# LEDThermometer.net
KiCad netlist of a schematic drawn in Altium Designer
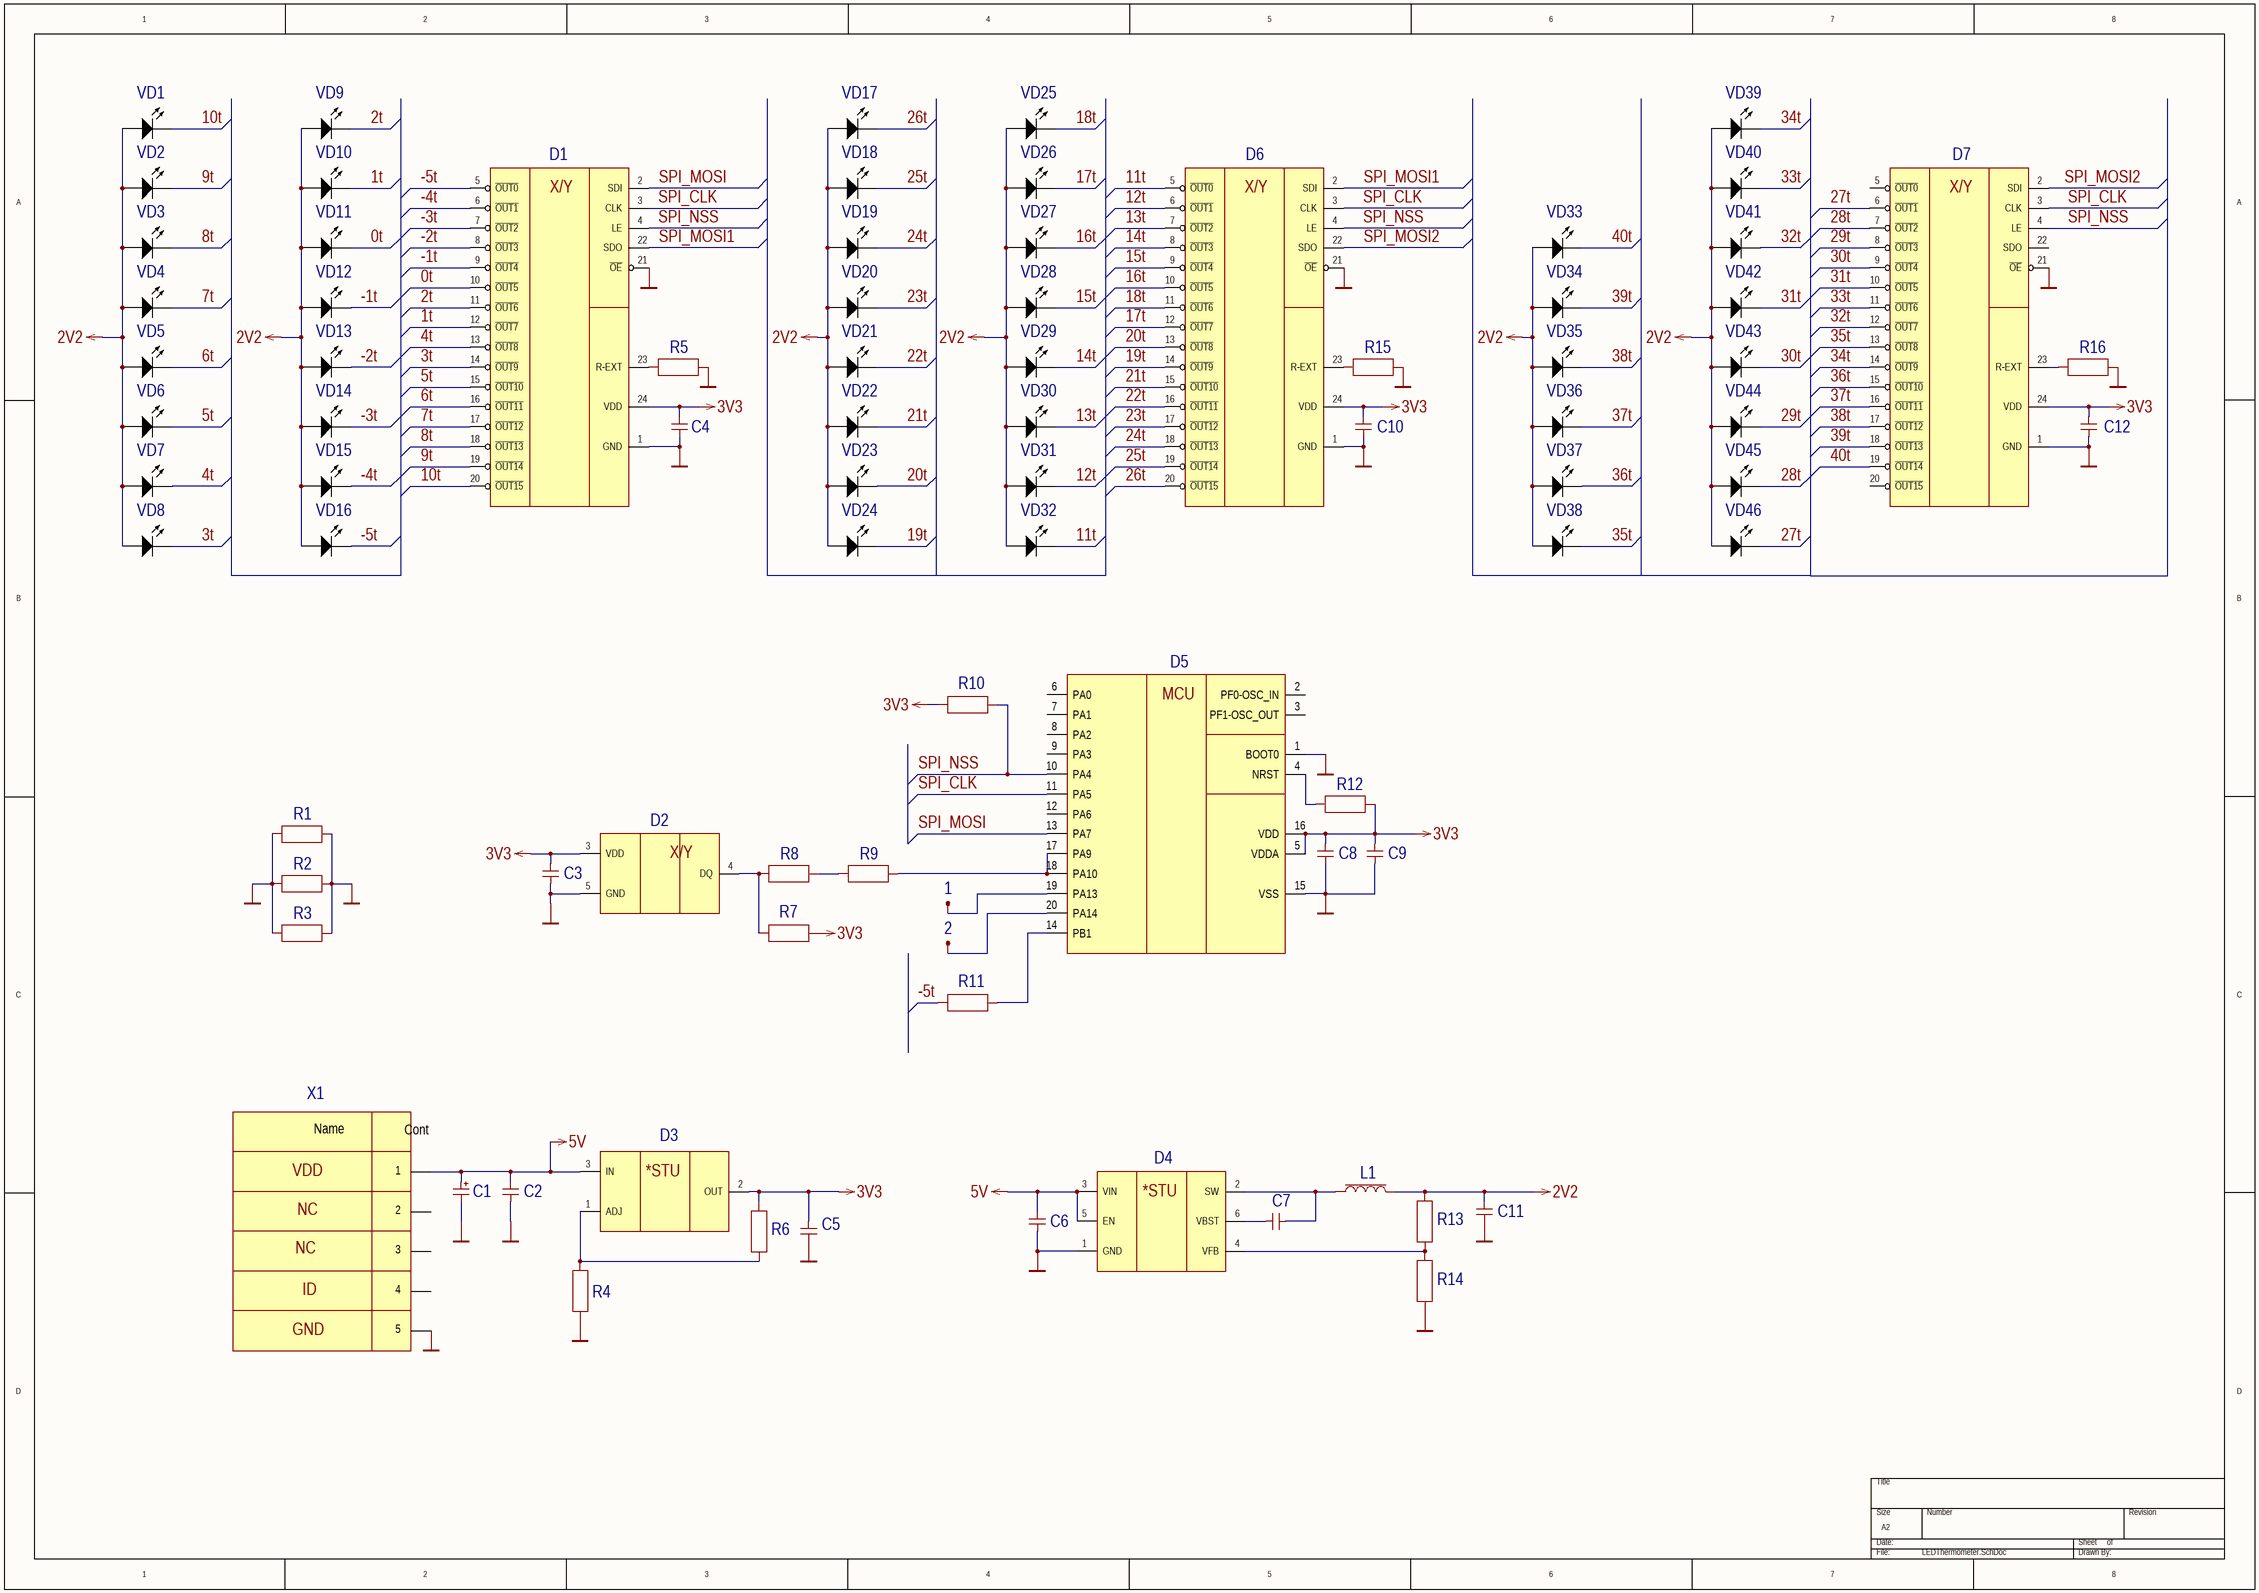
[diagram p0: LEDThermometer.SchDoc]

(export (version "E")
  (design (tool "Eeschema 10.0.6"))
  (components
    (comp (ref "1") (value "*") (footprint "point") (libsource (lib "Passive,Diodes") (part "Point")))
    (comp (ref "2") (value "*") (footprint "point") (libsource (lib "Passive,Diodes") (part "Point")))
    (comp (ref "C1")
      (value "D-20 V-47uF±10 %")
      (footprint "CAP POL 2917/7343")
      (description "Electrolytic capacitor")
      (libsource (lib "Passive,Diodes") (part "Cap_el"))
    )
    (comp (ref "C2")
      (value "0805-16 V-X7R-1uF±10 %")
      (footprint "SMD-0805C")
      (description "Capacitor")
      (libsource (lib "Passive,Diodes") (part "Cap"))
    )
    (comp (ref "C3")
      (value "0805-16 V-X7R-0.1uF±10 %")
      (footprint "SMD-0805C")
      (description "Capacitor")
      (libsource (lib "Passive,Diodes") (part "Cap"))
    )
    (comp (ref "C4")
      (value "0805-16 V-X7R-0.1uF±10 %")
      (footprint "SMD-0805C")
      (description "Capacitor")
      (libsource (lib "Passive,Diodes") (part "Cap"))
    )
    (comp (ref "C5")
      (value "0805-16 V-X7R-1uF±10 %")
      (footprint "SMD-0805C")
      (description "Capacitor")
      (libsource (lib "Passive,Diodes") (part "Cap"))
    )
    (comp (ref "C6")
      (value "0805-16 V-X7R-0.1uF±10 %")
      (footprint "SMD-0805C")
      (description "Capacitor")
      (libsource (lib "Passive,Diodes") (part "Cap"))
    )
    (comp (ref "C7")
      (value "0805-16 V-X7R-0.1uF±10 %")
      (footprint "SMD-0805C")
      (description "Capacitor")
      (libsource (lib "Passive,Diodes") (part "Cap"))
    )
    (comp (ref "C8")
      (value "0805-16 V-X7R-0.1uF±10 %")
      (footprint "SMD-0805C")
      (description "Capacitor")
      (libsource (lib "Passive,Diodes") (part "Cap"))
    )
    (comp (ref "C9")
      (value "0805-16 V-X7R-0.1uF±10 %")
      (footprint "SMD-0805C")
      (description "Capacitor")
      (libsource (lib "Passive,Diodes") (part "Cap"))
    )
    (comp (ref "C10")
      (value "0805-16 V-X7R-0.1uF±10 %")
      (footprint "SMD-0805C")
      (description "Capacitor")
      (libsource (lib "Passive,Diodes") (part "Cap"))
    )
    (comp (ref "C11")
      (value "1206-16 V-X7R-22uF±10 %")
      (footprint "SMD-1206C")
      (description "Capacitor")
      (libsource (lib "Passive,Diodes") (part "Cap"))
    )
    (comp (ref "C12")
      (value "0805-16 V-X7R-0.1uF±10 %")
      (footprint "SMD-0805C")
      (description "Capacitor")
      (libsource (lib "Passive,Diodes") (part "Cap"))
    )
    (comp (ref "D1")
      (value "MBI5039GF-B")
      (footprint "SOP24L")
      (description "16-Channel Constant Current LED Sink Driver with Silent Error Detection and Current Gain")
      (fields (field (name "MANUFACTURER") "Macroblock"))
      (libsource (lib "Devices") (part "MBI5039"))
    )
    (comp (ref "D2")
      (value "DS18B20Z+")
      (footprint "SO8_M")
      (description "Programmable Resolution 1-Wire Digital Thermometer")
      (fields (field (name "MANUFACTURER") "Maxim Integrated"))
      (libsource (lib "Devices") (part "DS18B20"))
    )
    (comp (ref "D3")
      (value "LM317DCYR")
      (footprint "SOT223_M")
      (description "3-Terminal Adjustable Regulator")
      (fields (field (name "MANUFACTURER") "Texas Instruments"))
      (libsource (lib "Devices") (part "LM317"))
    )
    (comp (ref "D4")
      (value "TPS562200DDCT")
      (footprint "SOT23-6_M")
      (description "4.5-V To 17-V Input, 2-A, 3-A Synchronous Step-Down Voltage Regulator")
      (fields (field (name "MANUFACTURER") "Texas Instruments"))
      (libsource (lib "Devices") (part "TPS562200"))
    )
    (comp (ref "D5")
      (value "STM32F030F4P6")
      (footprint "TSSOP-20")
      (fields (field (name "MANUFACTURER") "STMicroelectronics"))
      (libsource (lib "Devices") (part "STM32F030FxP"))
    )
    (comp (ref "D6")
      (value "MBI5039GF-B")
      (footprint "SOP24L")
      (description "16-Channel Constant Current LED Sink Driver with Silent Error Detection and Current Gain")
      (fields (field (name "MANUFACTURER") "Macroblock"))
      (libsource (lib "Devices") (part "MBI5039"))
    )
    (comp (ref "D7")
      (value "MBI5039GF-B")
      (footprint "SOP24L")
      (description "16-Channel Constant Current LED Sink Driver with Silent Error Detection and Current Gain")
      (fields (field (name "MANUFACTURER") "Macroblock"))
      (libsource (lib "Devices") (part "MBI5039"))
    )
    (comp (ref "L1")
      (value "NLCV32T-2R2M-EF")
      (footprint "1210_M")
      (description "Inductor")
      (fields (field (name "MANUFACTURER") "TDK"))
      (libsource (lib "Passive,Diodes") (part "Inductor"))
    )
    (comp (ref "R1")
      (value "0805±5 %-0 Ohm")
      (footprint "SMD-0805-RES")
      (description "Resistor")
      (libsource (lib "") (part "Res_2"))
    )
    (comp (ref "R2")
      (value "0805±5 %-0 Ohm")
      (footprint "SMD-0805-RES")
      (description "Resistor")
      (libsource (lib "") (part "Res_2"))
    )
    (comp (ref "R3")
      (value "0805±5 %-0 Ohm")
      (footprint "SMD-0805-RES")
      (description "Resistor")
      (libsource (lib "") (part "Res_2"))
    )
    (comp (ref "R4")
      (value "0805±1 %-2 kOhm")
      (footprint "SMD-0805-RES")
      (description "Resistor")
      (libsource (lib "") (part "Res_3"))
    )
    (comp (ref "R5")
      (value "0805±1 %-10 kOhm")
      (footprint "SMD-0805-RES")
      (description "Resistor")
      (libsource (lib "") (part "Res_2"))
    )
    (comp (ref "R6")
      (value "0805±1 %-1.3 kOhm")
      (footprint "SMD-0805-RES")
      (description "Resistor")
      (libsource (lib "") (part "Res_2"))
    )
    (comp (ref "R7")
      (value "0805±5 %-4.7 kOhm")
      (footprint "SMD-0805-RES")
      (description "Resistor")
      (libsource (lib "") (part "Res_1"))
    )
    (comp (ref "R8")
      (value "0805±5 %-0 Ohm")
      (footprint "SMD-0805-RES")
      (description "Resistor")
      (libsource (lib "") (part "Res_2"))
    )
    (comp (ref "R9")
      (value "0805±5 %-0 Ohm")
      (footprint "SMD-0805-RES")
      (description "Resistor")
      (libsource (lib "") (part "Res_2"))
    )
    (comp (ref "R10")
      (value "0805±5 %-10 kOhm")
      (footprint "SMD-0805-RES")
      (description "Resistor")
      (libsource (lib "Passive,Diodes") (part "Res"))
    )
    (comp (ref "R11")
      (value "DNP")
      (footprint "SMD-0805-RES")
      (description "Resistor")
      (libsource (lib "Passive,Diodes") (part "Res"))
    )
    (comp (ref "R12")
      (value "0805±5 %-10 kOhm")
      (footprint "SMD-0805-RES")
      (description "Resistor")
      (libsource (lib "") (part "Res_2"))
    )
    (comp (ref "R13")
      (value "0805±1 %-19.6 kOhm")
      (footprint "SMD-0805-RES")
      (description "Resistor")
      (libsource (lib "") (part "Res_2"))
    )
    (comp (ref "R14")
      (value "0805±1 %-10.2 kOhm")
      (footprint "SMD-0805-RES")
      (description "Resistor")
      (libsource (lib "") (part "Res_2"))
    )
    (comp (ref "R15")
      (value "0805±1 %-10 kOhm")
      (footprint "SMD-0805-RES")
      (description "Resistor")
      (libsource (lib "") (part "Res_2"))
    )
    (comp (ref "R16")
      (value "0805±1 %-10 kOhm")
      (footprint "SMD-0805-RES")
      (description "Resistor")
      (libsource (lib "") (part "Res_2"))
    )
    (comp (ref "VD1")
      (value "L-144IDT")
      (footprint "LED_1.9x3.9mm")
      (description "Typical INFRARED GaAs LED")
      (fields (field (name "MANUFACTURER") "Kingbright"))
      (libsource (lib "Passive,Diodes") (part "LED"))
    )
    (comp (ref "VD2")
      (value "L-144IDT")
      (footprint "LED_1.9x3.9mm")
      (description "Typical INFRARED GaAs LED")
      (fields (field (name "MANUFACTURER") "Kingbright"))
      (libsource (lib "Passive,Diodes") (part "LED"))
    )
    (comp (ref "VD3")
      (value "L-144IDT")
      (footprint "LED_1.9x3.9mm")
      (description "Typical INFRARED GaAs LED")
      (fields (field (name "MANUFACTURER") "Kingbright"))
      (libsource (lib "Passive,Diodes") (part "LED"))
    )
    (comp (ref "VD4")
      (value "L-144IDT")
      (footprint "LED_1.9x3.9mm")
      (description "Typical INFRARED GaAs LED")
      (fields (field (name "MANUFACTURER") "Kingbright"))
      (libsource (lib "Passive,Diodes") (part "LED"))
    )
    (comp (ref "VD5")
      (value "L-144IDT")
      (footprint "LED_1.9x3.9mm")
      (description "Typical INFRARED GaAs LED")
      (fields (field (name "MANUFACTURER") "Kingbright"))
      (libsource (lib "Passive,Diodes") (part "LED"))
    )
    (comp (ref "VD6")
      (value "L-144IDT")
      (footprint "LED_1.9x3.9mm")
      (description "Typical INFRARED GaAs LED")
      (fields (field (name "MANUFACTURER") "Kingbright"))
      (libsource (lib "Passive,Diodes") (part "LED"))
    )
    (comp (ref "VD7")
      (value "L-144IDT")
      (footprint "LED_1.9x3.9mm")
      (description "Typical INFRARED GaAs LED")
      (fields (field (name "MANUFACTURER") "Kingbright"))
      (libsource (lib "Passive,Diodes") (part "LED"))
    )
    (comp (ref "VD8")
      (value "L-144IDT")
      (footprint "LED_1.9x3.9mm")
      (description "Typical INFRARED GaAs LED")
      (fields (field (name "MANUFACTURER") "Kingbright"))
      (libsource (lib "Passive,Diodes") (part "LED"))
    )
    (comp (ref "VD9")
      (value "L-144IDT")
      (footprint "LED_1.9x3.9mm")
      (description "Typical INFRARED GaAs LED")
      (fields (field (name "MANUFACTURER") "Kingbright"))
      (libsource (lib "Passive,Diodes") (part "LED"))
    )
    (comp (ref "VD10")
      (value "L-144IDT")
      (footprint "LED_1.9x3.9mm")
      (description "Typical INFRARED GaAs LED")
      (fields (field (name "MANUFACTURER") "Kingbright"))
      (libsource (lib "Passive,Diodes") (part "LED"))
    )
    (comp (ref "VD11")
      (value "L-144IDT")
      (footprint "LED_1.9x3.9mm")
      (description "Typical INFRARED GaAs LED")
      (fields (field (name "MANUFACTURER") "Kingbright"))
      (libsource (lib "Passive,Diodes") (part "LED"))
    )
    (comp (ref "VD12")
      (value "L-144IDT")
      (footprint "LED_1.9x3.9mm")
      (description "Typical INFRARED GaAs LED")
      (fields (field (name "MANUFACTURER") "Kingbright"))
      (libsource (lib "Passive,Diodes") (part "LED"))
    )
    (comp (ref "VD13")
      (value "L-144IDT")
      (footprint "LED_1.9x3.9mm")
      (description "Typical INFRARED GaAs LED")
      (fields (field (name "MANUFACTURER") "Kingbright"))
      (libsource (lib "Passive,Diodes") (part "LED"))
    )
    (comp (ref "VD14")
      (value "L-144IDT")
      (footprint "LED_1.9x3.9mm")
      (description "Typical INFRARED GaAs LED")
      (fields (field (name "MANUFACTURER") "Kingbright"))
      (libsource (lib "Passive,Diodes") (part "LED"))
    )
    (comp (ref "VD15")
      (value "L-144IDT")
      (footprint "LED_1.9x3.9mm")
      (description "Typical INFRARED GaAs LED")
      (fields (field (name "MANUFACTURER") "Kingbright"))
      (libsource (lib "Passive,Diodes") (part "LED"))
    )
    (comp (ref "VD16")
      (value "L-793ID")
      (footprint "LED_8mm")
      (description "Typical INFRARED GaAs LED")
      (fields (field (name "MANUFACTURER") "Kingbright"))
      (libsource (lib "Passive,Diodes") (part "LED"))
    )
    (comp (ref "VD17")
      (value "L-144IDT")
      (footprint "LED_1.9x3.9mm")
      (description "Typical INFRARED GaAs LED")
      (fields (field (name "MANUFACTURER") "Kingbright"))
      (libsource (lib "Passive,Diodes") (part "LED"))
    )
    (comp (ref "VD18")
      (value "L-144IDT")
      (footprint "LED_1.9x3.9mm")
      (description "Typical INFRARED GaAs LED")
      (fields (field (name "MANUFACTURER") "Kingbright"))
      (libsource (lib "Passive,Diodes") (part "LED"))
    )
    (comp (ref "VD19")
      (value "L-144IDT")
      (footprint "LED_1.9x3.9mm")
      (description "Typical INFRARED GaAs LED")
      (fields (field (name "MANUFACTURER") "Kingbright"))
      (libsource (lib "Passive,Diodes") (part "LED"))
    )
    (comp (ref "VD20")
      (value "L-144IDT")
      (footprint "LED_1.9x3.9mm")
      (description "Typical INFRARED GaAs LED")
      (fields (field (name "MANUFACTURER") "Kingbright"))
      (libsource (lib "Passive,Diodes") (part "LED"))
    )
    (comp (ref "VD21")
      (value "L-144IDT")
      (footprint "LED_1.9x3.9mm")
      (description "Typical INFRARED GaAs LED")
      (fields (field (name "MANUFACTURER") "Kingbright"))
      (libsource (lib "Passive,Diodes") (part "LED"))
    )
    (comp (ref "VD22")
      (value "L-144IDT")
      (footprint "LED_1.9x3.9mm")
      (description "Typical INFRARED GaAs LED")
      (fields (field (name "MANUFACTURER") "Kingbright"))
      (libsource (lib "Passive,Diodes") (part "LED"))
    )
    (comp (ref "VD23")
      (value "L-144IDT")
      (footprint "LED_1.9x3.9mm")
      (description "Typical INFRARED GaAs LED")
      (fields (field (name "MANUFACTURER") "Kingbright"))
      (libsource (lib "Passive,Diodes") (part "LED"))
    )
    (comp (ref "VD24")
      (value "L-144IDT")
      (footprint "LED_1.9x3.9mm")
      (description "Typical INFRARED GaAs LED")
      (fields (field (name "MANUFACTURER") "Kingbright"))
      (libsource (lib "Passive,Diodes") (part "LED"))
    )
    (comp (ref "VD25")
      (value "L-144IDT")
      (footprint "LED_1.9x3.9mm")
      (description "Typical INFRARED GaAs LED")
      (fields (field (name "MANUFACTURER") "Kingbright"))
      (libsource (lib "Passive,Diodes") (part "LED"))
    )
    (comp (ref "VD26")
      (value "L-144IDT")
      (footprint "LED_1.9x3.9mm")
      (description "Typical INFRARED GaAs LED")
      (fields (field (name "MANUFACTURER") "Kingbright"))
      (libsource (lib "Passive,Diodes") (part "LED"))
    )
    (comp (ref "VD27")
      (value "L-144IDT")
      (footprint "LED_1.9x3.9mm")
      (description "Typical INFRARED GaAs LED")
      (fields (field (name "MANUFACTURER") "Kingbright"))
      (libsource (lib "Passive,Diodes") (part "LED"))
    )
    (comp (ref "VD28")
      (value "L-144IDT")
      (footprint "LED_1.9x3.9mm")
      (description "Typical INFRARED GaAs LED")
      (fields (field (name "MANUFACTURER") "Kingbright"))
      (libsource (lib "Passive,Diodes") (part "LED"))
    )
    (comp (ref "VD29")
      (value "L-144IDT")
      (footprint "LED_1.9x3.9mm")
      (description "Typical INFRARED GaAs LED")
      (fields (field (name "MANUFACTURER") "Kingbright"))
      (libsource (lib "Passive,Diodes") (part "LED"))
    )
    (comp (ref "VD30")
      (value "L-144IDT")
      (footprint "LED_1.9x3.9mm")
      (description "Typical INFRARED GaAs LED")
      (fields (field (name "MANUFACTURER") "Kingbright"))
      (libsource (lib "Passive,Diodes") (part "LED"))
    )
    (comp (ref "VD31")
      (value "L-144IDT")
      (footprint "LED_1.9x3.9mm")
      (description "Typical INFRARED GaAs LED")
      (fields (field (name "MANUFACTURER") "Kingbright"))
      (libsource (lib "Passive,Diodes") (part "LED"))
    )
    (comp (ref "VD32")
      (value "L-144IDT")
      (footprint "LED_1.9x3.9mm")
      (description "Typical INFRARED GaAs LED")
      (fields (field (name "MANUFACTURER") "Kingbright"))
      (libsource (lib "Passive,Diodes") (part "LED"))
    )
    (comp (ref "VD33")
      (value "L-144IDT")
      (footprint "LED_1.9x3.9mm")
      (description "Typical INFRARED GaAs LED")
      (fields (field (name "MANUFACTURER") "Kingbright"))
      (libsource (lib "Passive,Diodes") (part "LED"))
    )
    (comp (ref "VD34")
      (value "L-144IDT")
      (footprint "LED_1.9x3.9mm")
      (description "Typical INFRARED GaAs LED")
      (fields (field (name "MANUFACTURER") "Kingbright"))
      (libsource (lib "Passive,Diodes") (part "LED"))
    )
    (comp (ref "VD35")
      (value "L-144IDT")
      (footprint "LED_1.9x3.9mm")
      (description "Typical INFRARED GaAs LED")
      (fields (field (name "MANUFACTURER") "Kingbright"))
      (libsource (lib "Passive,Diodes") (part "LED"))
    )
    (comp (ref "VD36")
      (value "L-144IDT")
      (footprint "LED_1.9x3.9mm")
      (description "Typical INFRARED GaAs LED")
      (fields (field (name "MANUFACTURER") "Kingbright"))
      (libsource (lib "Passive,Diodes") (part "LED"))
    )
    (comp (ref "VD37")
      (value "L-144IDT")
      (footprint "LED_1.9x3.9mm")
      (description "Typical INFRARED GaAs LED")
      (fields (field (name "MANUFACTURER") "Kingbright"))
      (libsource (lib "Passive,Diodes") (part "LED"))
    )
    (comp (ref "VD38")
      (value "L-144IDT")
      (footprint "LED_1.9x3.9mm")
      (description "Typical INFRARED GaAs LED")
      (fields (field (name "MANUFACTURER") "Kingbright"))
      (libsource (lib "Passive,Diodes") (part "LED"))
    )
    (comp (ref "VD39")
      (value "L-144IDT")
      (footprint "LED_1.9x3.9mm")
      (description "Typical INFRARED GaAs LED")
      (fields (field (name "MANUFACTURER") "Kingbright"))
      (libsource (lib "Passive,Diodes") (part "LED"))
    )
    (comp (ref "VD40")
      (value "L-144IDT")
      (footprint "LED_1.9x3.9mm")
      (description "Typical INFRARED GaAs LED")
      (fields (field (name "MANUFACTURER") "Kingbright"))
      (libsource (lib "Passive,Diodes") (part "LED"))
    )
    (comp (ref "VD41")
      (value "L-144IDT")
      (footprint "LED_1.9x3.9mm")
      (description "Typical INFRARED GaAs LED")
      (fields (field (name "MANUFACTURER") "Kingbright"))
      (libsource (lib "Passive,Diodes") (part "LED"))
    )
    (comp (ref "VD42")
      (value "L-144IDT")
      (footprint "LED_1.9x3.9mm")
      (description "Typical INFRARED GaAs LED")
      (fields (field (name "MANUFACTURER") "Kingbright"))
      (libsource (lib "Passive,Diodes") (part "LED"))
    )
    (comp (ref "VD43")
      (value "L-144IDT")
      (footprint "LED_1.9x3.9mm")
      (description "Typical INFRARED GaAs LED")
      (fields (field (name "MANUFACTURER") "Kingbright"))
      (libsource (lib "Passive,Diodes") (part "LED"))
    )
    (comp (ref "VD44")
      (value "L-144IDT")
      (footprint "LED_1.9x3.9mm")
      (description "Typical INFRARED GaAs LED")
      (fields (field (name "MANUFACTURER") "Kingbright"))
      (libsource (lib "Passive,Diodes") (part "LED"))
    )
    (comp (ref "VD45")
      (value "L-144IDT")
      (footprint "LED_1.9x3.9mm")
      (description "Typical INFRARED GaAs LED")
      (fields (field (name "MANUFACTURER") "Kingbright"))
      (libsource (lib "Passive,Diodes") (part "LED"))
    )
    (comp (ref "VD46")
      (value "L-144IDT")
      (footprint "LED_1.9x3.9mm")
      (description "Typical INFRARED GaAs LED")
      (fields (field (name "MANUFACTURER") "Kingbright"))
      (libsource (lib "Passive,Diodes") (part "LED"))
    )
    (comp (ref "X1")
      (value "DS1104-B60SRS")
      (footprint "Mini-USB-B")
      (description "Mini USB-B connector")
      (fields (field (name "MANUFACTURER") "Connfly Electronics"))
      (libsource (lib "Connectors") (part "MINI-USB-B"))
    )
  )
  (nets
    (net (code "1") (name "/-1t") (class "Default")
      (node (ref "D1") (pin "9") (pinfunction "~{OUT4}_9") (pintype "passive"))
      (node (ref "VD12") (pin "2") (pinfunction "K_2") (pintype "passive"))
    )
    (net (code "2") (name "/-2t") (class "Default")
      (node (ref "D1") (pin "8") (pinfunction "~{OUT3}_8") (pintype "passive"))
      (node (ref "VD13") (pin "2") (pinfunction "K_2") (pintype "passive"))
    )
    (net (code "3") (name "/-3t") (class "Default")
      (node (ref "D1") (pin "7") (pinfunction "~{OUT2}_7") (pintype "passive"))
      (node (ref "VD14") (pin "2") (pinfunction "K_2") (pintype "passive"))
    )
    (net (code "4") (name "/-4t") (class "Default")
      (node (ref "D1") (pin "6") (pinfunction "~{OUT1}_6") (pintype "passive"))
      (node (ref "VD15") (pin "2") (pinfunction "K_2") (pintype "passive"))
    )
    (net (code "5") (name "/-5t") (class "Default")
      (node (ref "D1") (pin "5") (pinfunction "~{OUT0}_5") (pintype "passive"))
      (node (ref "R11") (pin "1") (pinfunction "1_1") (pintype "passive"))
      (node (ref "VD16") (pin "2") (pinfunction "K_2") (pintype "passive"))
    )
    (net (code "6") (name "/0t") (class "Default")
      (node (ref "D1") (pin "10") (pinfunction "~{OUT5}_10") (pintype "passive"))
      (node (ref "VD11") (pin "2") (pinfunction "K_2") (pintype "passive"))
    )
    (net (code "7") (name "/1t") (class "Default")
      (node (ref "D1") (pin "12") (pinfunction "~{OUT7}_12") (pintype "passive"))
      (node (ref "VD10") (pin "2") (pinfunction "K_2") (pintype "passive"))
    )
    (net (code "8") (name "/2t") (class "Default")
      (node (ref "D1") (pin "11") (pinfunction "~{OUT6}_11") (pintype "passive"))
      (node (ref "VD9") (pin "2") (pinfunction "K_2") (pintype "passive"))
    )
    (net (code "9") (name "/3t") (class "Default")
      (node (ref "D1") (pin "14") (pinfunction "~{OUT9}_14") (pintype "passive"))
      (node (ref "VD8") (pin "2") (pinfunction "K_2") (pintype "passive"))
    )
    (net (code "10") (name "/4t") (class "Default")
      (node (ref "D1") (pin "13") (pinfunction "~{OUT8}_13") (pintype "passive"))
      (node (ref "VD7") (pin "2") (pinfunction "K_2") (pintype "passive"))
    )
    (net (code "11") (name "/5t") (class "Default")
      (node (ref "D1") (pin "15") (pinfunction "~{OUT10}_15") (pintype "passive"))
      (node (ref "VD6") (pin "2") (pinfunction "K_2") (pintype "passive"))
    )
    (net (code "12") (name "/6t") (class "Default")
      (node (ref "D1") (pin "16") (pinfunction "~{OUT11}_16") (pintype "passive"))
      (node (ref "VD5") (pin "2") (pinfunction "K_2") (pintype "passive"))
    )
    (net (code "13") (name "/7t") (class "Default")
      (node (ref "D1") (pin "17") (pinfunction "~{OUT12}_17") (pintype "passive"))
      (node (ref "VD4") (pin "2") (pinfunction "K_2") (pintype "passive"))
    )
    (net (code "14") (name "/8t") (class "Default")
      (node (ref "D1") (pin "18") (pinfunction "~{OUT13}_18") (pintype "passive"))
      (node (ref "VD3") (pin "2") (pinfunction "K_2") (pintype "passive"))
    )
    (net (code "15") (name "/9t") (class "Default")
      (node (ref "D1") (pin "19") (pinfunction "~{OUT14}_19") (pintype "passive"))
      (node (ref "VD2") (pin "2") (pinfunction "K_2") (pintype "passive"))
    )
    (net (code "16") (name "/10t") (class "Default")
      (node (ref "D1") (pin "20") (pinfunction "~{OUT15}_20") (pintype "passive"))
      (node (ref "VD1") (pin "2") (pinfunction "K_2") (pintype "passive"))
    )
    (net (code "17") (name "/11t") (class "Default")
      (node (ref "D6") (pin "5") (pinfunction "~{OUT0}_5") (pintype "passive"))
      (node (ref "VD32") (pin "2") (pinfunction "K_2") (pintype "passive"))
    )
    (net (code "18") (name "/12t") (class "Default")
      (node (ref "D6") (pin "6") (pinfunction "~{OUT1}_6") (pintype "passive"))
      (node (ref "VD31") (pin "2") (pinfunction "K_2") (pintype "passive"))
    )
    (net (code "19") (name "/13t") (class "Default")
      (node (ref "D6") (pin "7") (pinfunction "~{OUT2}_7") (pintype "passive"))
      (node (ref "VD30") (pin "2") (pinfunction "K_2") (pintype "passive"))
    )
    (net (code "20") (name "/14t") (class "Default")
      (node (ref "D6") (pin "8") (pinfunction "~{OUT3}_8") (pintype "passive"))
      (node (ref "VD29") (pin "2") (pinfunction "K_2") (pintype "passive"))
    )
    (net (code "21") (name "/15t") (class "Default")
      (node (ref "D6") (pin "9") (pinfunction "~{OUT4}_9") (pintype "passive"))
      (node (ref "VD28") (pin "2") (pinfunction "K_2") (pintype "passive"))
    )
    (net (code "22") (name "/16t") (class "Default")
      (node (ref "D6") (pin "10") (pinfunction "~{OUT5}_10") (pintype "passive"))
      (node (ref "VD27") (pin "2") (pinfunction "K_2") (pintype "passive"))
    )
    (net (code "23") (name "/17t") (class "Default")
      (node (ref "D6") (pin "12") (pinfunction "~{OUT7}_12") (pintype "passive"))
      (node (ref "VD26") (pin "2") (pinfunction "K_2") (pintype "passive"))
    )
    (net (code "24") (name "/18t") (class "Default")
      (node (ref "D6") (pin "11") (pinfunction "~{OUT6}_11") (pintype "passive"))
      (node (ref "VD25") (pin "2") (pinfunction "K_2") (pintype "passive"))
    )
    (net (code "25") (name "/19t") (class "Default")
      (node (ref "D6") (pin "14") (pinfunction "~{OUT9}_14") (pintype "passive"))
      (node (ref "VD24") (pin "2") (pinfunction "K_2") (pintype "passive"))
    )
    (net (code "26") (name "/20t") (class "Default")
      (node (ref "D6") (pin "13") (pinfunction "~{OUT8}_13") (pintype "passive"))
      (node (ref "VD23") (pin "2") (pinfunction "K_2") (pintype "passive"))
    )
    (net (code "27") (name "/21t") (class "Default")
      (node (ref "D6") (pin "15") (pinfunction "~{OUT10}_15") (pintype "passive"))
      (node (ref "VD22") (pin "2") (pinfunction "K_2") (pintype "passive"))
    )
    (net (code "28") (name "/22t") (class "Default")
      (node (ref "D6") (pin "16") (pinfunction "~{OUT11}_16") (pintype "passive"))
      (node (ref "VD21") (pin "2") (pinfunction "K_2") (pintype "passive"))
    )
    (net (code "29") (name "/23t") (class "Default")
      (node (ref "D6") (pin "17") (pinfunction "~{OUT12}_17") (pintype "passive"))
      (node (ref "VD20") (pin "2") (pinfunction "K_2") (pintype "passive"))
    )
    (net (code "30") (name "/24t") (class "Default")
      (node (ref "D6") (pin "18") (pinfunction "~{OUT13}_18") (pintype "passive"))
      (node (ref "VD19") (pin "2") (pinfunction "K_2") (pintype "passive"))
    )
    (net (code "31") (name "/25t") (class "Default")
      (node (ref "D6") (pin "19") (pinfunction "~{OUT14}_19") (pintype "passive"))
      (node (ref "VD18") (pin "2") (pinfunction "K_2") (pintype "passive"))
    )
    (net (code "32") (name "/26t") (class "Default")
      (node (ref "D6") (pin "20") (pinfunction "~{OUT15}_20") (pintype "passive"))
      (node (ref "VD17") (pin "2") (pinfunction "K_2") (pintype "passive"))
    )
    (net (code "33") (name "/27t") (class "Default")
      (node (ref "D7") (pin "6") (pinfunction "~{OUT1}_6") (pintype "passive"))
      (node (ref "VD46") (pin "2") (pinfunction "K_2") (pintype "passive"))
    )
    (net (code "34") (name "/28t") (class "Default")
      (node (ref "D7") (pin "7") (pinfunction "~{OUT2}_7") (pintype "passive"))
      (node (ref "VD45") (pin "2") (pinfunction "K_2") (pintype "passive"))
    )
    (net (code "35") (name "/29t") (class "Default")
      (node (ref "D7") (pin "8") (pinfunction "~{OUT3}_8") (pintype "passive"))
      (node (ref "VD44") (pin "2") (pinfunction "K_2") (pintype "passive"))
    )
    (net (code "36") (name "/30t") (class "Default")
      (node (ref "D7") (pin "9") (pinfunction "~{OUT4}_9") (pintype "passive"))
      (node (ref "VD43") (pin "2") (pinfunction "K_2") (pintype "passive"))
    )
    (net (code "37") (name "/31t") (class "Default")
      (node (ref "D7") (pin "10") (pinfunction "~{OUT5}_10") (pintype "passive"))
      (node (ref "VD42") (pin "2") (pinfunction "K_2") (pintype "passive"))
    )
    (net (code "38") (name "/32t") (class "Default")
      (node (ref "D7") (pin "12") (pinfunction "~{OUT7}_12") (pintype "passive"))
      (node (ref "VD41") (pin "2") (pinfunction "K_2") (pintype "passive"))
    )
    (net (code "39") (name "/33t") (class "Default")
      (node (ref "D7") (pin "11") (pinfunction "~{OUT6}_11") (pintype "passive"))
      (node (ref "VD40") (pin "2") (pinfunction "K_2") (pintype "passive"))
    )
    (net (code "40") (name "/34t") (class "Default")
      (node (ref "D7") (pin "14") (pinfunction "~{OUT9}_14") (pintype "passive"))
      (node (ref "VD39") (pin "2") (pinfunction "K_2") (pintype "passive"))
    )
    (net (code "41") (name "/35t") (class "Default")
      (node (ref "D7") (pin "13") (pinfunction "~{OUT8}_13") (pintype "passive"))
      (node (ref "VD38") (pin "2") (pinfunction "K_2") (pintype "passive"))
    )
    (net (code "42") (name "/36t") (class "Default")
      (node (ref "D7") (pin "15") (pinfunction "~{OUT10}_15") (pintype "passive"))
      (node (ref "VD37") (pin "2") (pinfunction "K_2") (pintype "passive"))
    )
    (net (code "43") (name "/37t") (class "Default")
      (node (ref "D7") (pin "16") (pinfunction "~{OUT11}_16") (pintype "passive"))
      (node (ref "VD36") (pin "2") (pinfunction "K_2") (pintype "passive"))
    )
    (net (code "44") (name "/38t") (class "Default")
      (node (ref "D7") (pin "17") (pinfunction "~{OUT12}_17") (pintype "passive"))
      (node (ref "VD35") (pin "2") (pinfunction "K_2") (pintype "passive"))
    )
    (net (code "45") (name "/39t") (class "Default")
      (node (ref "D7") (pin "18") (pinfunction "~{OUT13}_18") (pintype "passive"))
      (node (ref "VD34") (pin "2") (pinfunction "K_2") (pintype "passive"))
    )
    (net (code "46") (name "/40t") (class "Default")
      (node (ref "D7") (pin "19") (pinfunction "~{OUT14}_19") (pintype "passive"))
      (node (ref "VD33") (pin "2") (pinfunction "K_2") (pintype "passive"))
    )
    (net (code "47") (name "/SPI_CLK") (class "Default")
      (node (ref "D1") (pin "3") (pinfunction "CLK_3") (pintype "passive"))
      (node (ref "D5") (pin "11") (pinfunction "PA5_11") (pintype "passive"))
      (node (ref "D6") (pin "3") (pinfunction "CLK_3") (pintype "passive"))
      (node (ref "D7") (pin "3") (pinfunction "CLK_3") (pintype "passive"))
    )
    (net (code "48") (name "/SPI_MOSI") (class "Default")
      (node (ref "D1") (pin "2") (pinfunction "SDI_2") (pintype "passive"))
      (node (ref "D5") (pin "13") (pinfunction "PA7_13") (pintype "passive"))
    )
    (net (code "49") (name "/SPI_MOSI1") (class "Default")
      (node (ref "D1") (pin "22") (pinfunction "SDO_22") (pintype "passive"))
      (node (ref "D6") (pin "2") (pinfunction "SDI_2") (pintype "passive"))
    )
    (net (code "50") (name "/SPI_MOSI2") (class "Default")
      (node (ref "D6") (pin "22") (pinfunction "SDO_22") (pintype "passive"))
      (node (ref "D7") (pin "2") (pinfunction "SDI_2") (pintype "passive"))
    )
    (net (code "51") (name "/SPI_NSS") (class "Default")
      (node (ref "D1") (pin "4") (pinfunction "LE_4") (pintype "passive"))
      (node (ref "D5") (pin "10") (pinfunction "PA4_10") (pintype "passive"))
      (node (ref "D6") (pin "4") (pinfunction "LE_4") (pintype "passive"))
      (node (ref "D7") (pin "4") (pinfunction "LE_4") (pintype "passive"))
      (node (ref "R10") (pin "2") (pinfunction "2_2") (pintype "passive"))
    )
    (net (code "52") (name "2V2") (class "Default")
      (node (ref "C11") (pin "2") (pinfunction "2_2") (pintype "passive"))
      (node (ref "L1") (pin "2") (pinfunction "2_2") (pintype "passive"))
      (node (ref "R13") (pin "2") (pinfunction "2_2") (pintype "passive"))
      (node (ref "VD1") (pin "1") (pinfunction "A_1") (pintype "passive"))
      (node (ref "VD10") (pin "1") (pinfunction "A_1") (pintype "passive"))
      (node (ref "VD11") (pin "1") (pinfunction "A_1") (pintype "passive"))
      (node (ref "VD12") (pin "1") (pinfunction "A_1") (pintype "passive"))
      (node (ref "VD13") (pin "1") (pinfunction "A_1") (pintype "passive"))
      (node (ref "VD14") (pin "1") (pinfunction "A_1") (pintype "passive"))
      (node (ref "VD15") (pin "1") (pinfunction "A_1") (pintype "passive"))
      (node (ref "VD16") (pin "1") (pinfunction "A_1") (pintype "passive"))
      (node (ref "VD17") (pin "1") (pinfunction "A_1") (pintype "passive"))
      (node (ref "VD18") (pin "1") (pinfunction "A_1") (pintype "passive"))
      (node (ref "VD19") (pin "1") (pinfunction "A_1") (pintype "passive"))
      (node (ref "VD2") (pin "1") (pinfunction "A_1") (pintype "passive"))
      (node (ref "VD20") (pin "1") (pinfunction "A_1") (pintype "passive"))
      (node (ref "VD21") (pin "1") (pinfunction "A_1") (pintype "passive"))
      (node (ref "VD22") (pin "1") (pinfunction "A_1") (pintype "passive"))
      (node (ref "VD23") (pin "1") (pinfunction "A_1") (pintype "passive"))
      (node (ref "VD24") (pin "1") (pinfunction "A_1") (pintype "passive"))
      (node (ref "VD25") (pin "1") (pinfunction "A_1") (pintype "passive"))
      (node (ref "VD26") (pin "1") (pinfunction "A_1") (pintype "passive"))
      (node (ref "VD27") (pin "1") (pinfunction "A_1") (pintype "passive"))
      (node (ref "VD28") (pin "1") (pinfunction "A_1") (pintype "passive"))
      (node (ref "VD29") (pin "1") (pinfunction "A_1") (pintype "passive"))
      (node (ref "VD3") (pin "1") (pinfunction "A_1") (pintype "passive"))
      (node (ref "VD30") (pin "1") (pinfunction "A_1") (pintype "passive"))
      (node (ref "VD31") (pin "1") (pinfunction "A_1") (pintype "passive"))
      (node (ref "VD32") (pin "1") (pinfunction "A_1") (pintype "passive"))
      (node (ref "VD33") (pin "1") (pinfunction "A_1") (pintype "passive"))
      (node (ref "VD34") (pin "1") (pinfunction "A_1") (pintype "passive"))
      (node (ref "VD35") (pin "1") (pinfunction "A_1") (pintype "passive"))
      (node (ref "VD36") (pin "1") (pinfunction "A_1") (pintype "passive"))
      (node (ref "VD37") (pin "1") (pinfunction "A_1") (pintype "passive"))
      (node (ref "VD38") (pin "1") (pinfunction "A_1") (pintype "passive"))
      (node (ref "VD39") (pin "1") (pinfunction "A_1") (pintype "passive"))
      (node (ref "VD4") (pin "1") (pinfunction "A_1") (pintype "passive"))
      (node (ref "VD40") (pin "1") (pinfunction "A_1") (pintype "passive"))
      (node (ref "VD41") (pin "1") (pinfunction "A_1") (pintype "passive"))
      (node (ref "VD42") (pin "1") (pinfunction "A_1") (pintype "passive"))
      (node (ref "VD43") (pin "1") (pinfunction "A_1") (pintype "passive"))
      (node (ref "VD44") (pin "1") (pinfunction "A_1") (pintype "passive"))
      (node (ref "VD45") (pin "1") (pinfunction "A_1") (pintype "passive"))
      (node (ref "VD46") (pin "1") (pinfunction "A_1") (pintype "passive"))
      (node (ref "VD5") (pin "1") (pinfunction "A_1") (pintype "passive"))
      (node (ref "VD6") (pin "1") (pinfunction "A_1") (pintype "passive"))
      (node (ref "VD7") (pin "1") (pinfunction "A_1") (pintype "passive"))
      (node (ref "VD8") (pin "1") (pinfunction "A_1") (pintype "passive"))
      (node (ref "VD9") (pin "1") (pinfunction "A_1") (pintype "passive"))
    )
    (net (code "53") (name "3V3") (class "Default")
      (node (ref "C10") (pin "2") (pinfunction "2_2") (pintype "passive"))
      (node (ref "C12") (pin "2") (pinfunction "2_2") (pintype "passive"))
      (node (ref "C3") (pin "2") (pinfunction "2_2") (pintype "passive"))
      (node (ref "C4") (pin "2") (pinfunction "2_2") (pintype "passive"))
      (node (ref "C5") (pin "2") (pinfunction "2_2") (pintype "passive"))
      (node (ref "C8") (pin "2") (pinfunction "2_2") (pintype "passive"))
      (node (ref "C9") (pin "2") (pinfunction "2_2") (pintype "passive"))
      (node (ref "D1") (pin "24") (pinfunction "VDD_24") (pintype "power_in"))
      (node (ref "D2") (pin "3") (pinfunction "VDD_3") (pintype "passive"))
      (node (ref "D3") (pin "2") (pinfunction "OUT_2") (pintype "power_in"))
      (node (ref "D5") (pin "16") (pinfunction "VDD_16") (pintype "power_in"))
      (node (ref "D5") (pin "5") (pinfunction "VDDA_5") (pintype "power_in"))
      (node (ref "D6") (pin "24") (pinfunction "VDD_24") (pintype "power_in"))
      (node (ref "D7") (pin "24") (pinfunction "VDD_24") (pintype "power_in"))
      (node (ref "R10") (pin "1") (pinfunction "1_1") (pintype "passive"))
      (node (ref "R12") (pin "2") (pinfunction "2_2") (pintype "passive"))
      (node (ref "R6") (pin "2") (pinfunction "2_2") (pintype "passive"))
      (node (ref "R7") (pin "1") (pinfunction "1_1") (pintype "passive"))
    )
    (net (code "54") (name "5V") (class "Default")
      (node (ref "C1") (pin "1") (pinfunction "1_1") (pintype "passive"))
      (node (ref "C2") (pin "2") (pinfunction "2_2") (pintype "passive"))
      (node (ref "C6") (pin "2") (pinfunction "2_2") (pintype "passive"))
      (node (ref "D3") (pin "3") (pinfunction "IN_3") (pintype "power_in"))
      (node (ref "D4") (pin "3") (pinfunction "VIN_3") (pintype "power_in"))
      (node (ref "D4") (pin "5") (pinfunction "EN_5") (pintype "passive"))
      (node (ref "X1") (pin "1") (pinfunction "1_1") (pintype "passive"))
    )
    (net (code "55") (name "GND") (class "Default")
      (node (ref "C1") (pin "2") (pinfunction "2_2") (pintype "passive"))
      (node (ref "C10") (pin "1") (pinfunction "1_1") (pintype "passive"))
      (node (ref "C11") (pin "1") (pinfunction "1_1") (pintype "passive"))
      (node (ref "C12") (pin "1") (pinfunction "1_1") (pintype "passive"))
      (node (ref "C2") (pin "1") (pinfunction "1_1") (pintype "passive"))
      (node (ref "C3") (pin "1") (pinfunction "1_1") (pintype "passive"))
      (node (ref "C4") (pin "1") (pinfunction "1_1") (pintype "passive"))
      (node (ref "C5") (pin "1") (pinfunction "1_1") (pintype "passive"))
      (node (ref "C6") (pin "1") (pinfunction "1_1") (pintype "passive"))
      (node (ref "C8") (pin "1") (pinfunction "1_1") (pintype "passive"))
      (node (ref "C9") (pin "1") (pinfunction "1_1") (pintype "passive"))
      (node (ref "D1") (pin "1") (pinfunction "GND_1") (pintype "power_in"))
      (node (ref "D1") (pin "21") (pinfunction "~{OE}_21") (pintype "passive"))
      (node (ref "D2") (pin "5") (pinfunction "GND_5") (pintype "power_in"))
      (node (ref "D4") (pin "1") (pinfunction "GND_1") (pintype "power_in"))
      (node (ref "D5") (pin "1") (pinfunction "BOOT0_1") (pintype "passive"))
      (node (ref "D5") (pin "15") (pinfunction "VSS_15") (pintype "power_in"))
      (node (ref "D6") (pin "1") (pinfunction "GND_1") (pintype "power_in"))
      (node (ref "D6") (pin "21") (pinfunction "~{OE}_21") (pintype "passive"))
      (node (ref "D7") (pin "1") (pinfunction "GND_1") (pintype "power_in"))
      (node (ref "D7") (pin "21") (pinfunction "~{OE}_21") (pintype "passive"))
      (node (ref "R1") (pin "1") (pinfunction "1_1") (pintype "passive"))
      (node (ref "R1") (pin "2") (pinfunction "2_2") (pintype "passive"))
      (node (ref "R14") (pin "1") (pinfunction "1_1") (pintype "passive"))
      (node (ref "R15") (pin "2") (pinfunction "2_2") (pintype "passive"))
      (node (ref "R16") (pin "2") (pinfunction "2_2") (pintype "passive"))
      (node (ref "R2") (pin "1") (pinfunction "1_1") (pintype "passive"))
      (node (ref "R2") (pin "2") (pinfunction "2_2") (pintype "passive"))
      (node (ref "R3") (pin "1") (pinfunction "1_1") (pintype "passive"))
      (node (ref "R3") (pin "2") (pinfunction "2_2") (pintype "passive"))
      (node (ref "R4") (pin "2") (pinfunction "2_2") (pintype "passive"))
      (node (ref "R5") (pin "2") (pinfunction "2_2") (pintype "passive"))
      (node (ref "X1") (pin "5") (pinfunction "5_5") (pintype "passive"))
    )
    (net (code "56") (name "Net-(D1-R-EXT)") (class "Default")
      (node (ref "D1") (pin "23") (pinfunction "R-EXT_23") (pintype "passive"))
      (node (ref "R5") (pin "1") (pinfunction "1_1") (pintype "passive"))
    )
    (net (code "57") (name "Net-(D2-DQ)") (class "Default")
      (node (ref "D2") (pin "4") (pinfunction "DQ_4") (pintype "passive"))
      (node (ref "R7") (pin "2") (pinfunction "2_2") (pintype "passive"))
      (node (ref "R8") (pin "1") (pinfunction "1_1") (pintype "passive"))
    )
    (net (code "58") (name "Net-(D3-ADJ)") (class "Default")
      (node (ref "D3") (pin "1") (pinfunction "ADJ_1") (pintype "passive"))
      (node (ref "R4") (pin "1") (pinfunction "1_1") (pintype "passive"))
      (node (ref "R6") (pin "1") (pinfunction "1_1") (pintype "passive"))
    )
    (net (code "59") (name "Net-(D4-SW)") (class "Default")
      (node (ref "C7") (pin "1") (pinfunction "1_1") (pintype "passive"))
      (node (ref "D4") (pin "2") (pinfunction "SW_2") (pintype "passive"))
      (node (ref "L1") (pin "1") (pinfunction "1_1") (pintype "passive"))
    )
    (net (code "60") (name "Net-(D4-VBST)") (class "Default")
      (node (ref "C7") (pin "2") (pinfunction "2_2") (pintype "passive"))
      (node (ref "D4") (pin "6") (pinfunction "VBST_6") (pintype "passive"))
    )
    (net (code "61") (name "Net-(D4-VFB)") (class "Default")
      (node (ref "D4") (pin "4") (pinfunction "VFB_4") (pintype "passive"))
      (node (ref "R13") (pin "1") (pinfunction "1_1") (pintype "passive"))
      (node (ref "R14") (pin "2") (pinfunction "2_2") (pintype "passive"))
    )
    (net (code "62") (name "Net-(D5-NRST)") (class "Default")
      (node (ref "D5") (pin "4") (pinfunction "NRST_4") (pintype "passive"))
      (node (ref "R12") (pin "1") (pinfunction "1_1") (pintype "passive"))
    )
    (net (code "63") (name "Net-(D5-PA10)") (class "Default")
      (node (ref "D5") (pin "17") (pinfunction "PA9_17") (pintype "passive"))
      (node (ref "D5") (pin "18") (pinfunction "PA10_18") (pintype "passive"))
      (node (ref "R9") (pin "2") (pinfunction "2_2") (pintype "passive"))
    )
    (net (code "64") (name "Net-(D5-PA13)") (class "Default")
      (node (ref "1") (pin "1") (pintype "passive"))
      (node (ref "D5") (pin "19") (pinfunction "PA13_19") (pintype "passive"))
    )
    (net (code "65") (name "Net-(D5-PA14)") (class "Default")
      (node (ref "2") (pin "1") (pintype "passive"))
      (node (ref "D5") (pin "20") (pinfunction "PA14_20") (pintype "passive"))
    )
    (net (code "66") (name "Net-(D5-PB1)") (class "Default")
      (node (ref "D5") (pin "14") (pinfunction "PB1_14") (pintype "passive"))
      (node (ref "R11") (pin "2") (pinfunction "2_2") (pintype "passive"))
    )
    (net (code "67") (name "Net-(D6-R-EXT)") (class "Default")
      (node (ref "D6") (pin "23") (pinfunction "R-EXT_23") (pintype "passive"))
      (node (ref "R15") (pin "1") (pinfunction "1_1") (pintype "passive"))
    )
    (net (code "68") (name "Net-(D7-R-EXT)") (class "Default")
      (node (ref "D7") (pin "23") (pinfunction "R-EXT_23") (pintype "passive"))
      (node (ref "R16") (pin "1") (pinfunction "1_1") (pintype "passive"))
    )
    (net (code "69") (name "Net-(R8-Pad2)") (class "Default")
      (node (ref "R8") (pin "2") (pinfunction "2_2") (pintype "passive"))
      (node (ref "R9") (pin "1") (pinfunction "1_1") (pintype "passive"))
    )
    (net (code "70") (name "unconnected-(D5-PA0-Pad6)") (class "Default")
      (node (ref "D5") (pin "6") (pinfunction "PA0_6") (pintype "passive"))
    )
    (net (code "71") (name "unconnected-(D5-PA1-Pad7)") (class "Default")
      (node (ref "D5") (pin "7") (pinfunction "PA1_7") (pintype "passive"))
    )
    (net (code "72") (name "unconnected-(D5-PA2-Pad8)") (class "Default")
      (node (ref "D5") (pin "8") (pinfunction "PA2_8") (pintype "passive"))
    )
    (net (code "73") (name "unconnected-(D5-PA3-Pad9)") (class "Default")
      (node (ref "D5") (pin "9") (pinfunction "PA3_9") (pintype "passive"))
    )
    (net (code "74") (name "unconnected-(D5-PA6-Pad12)") (class "Default")
      (node (ref "D5") (pin "12") (pinfunction "PA6_12") (pintype "passive"))
    )
    (net (code "75") (name "unconnected-(D5-PF0-OSC_IN-Pad2)") (class "Default")
      (node (ref "D5") (pin "2") (pinfunction "PF0-OSC_IN_2") (pintype "passive"))
    )
    (net (code "76") (name "unconnected-(D5-PF1-OSC_OUT-Pad3)") (class "Default")
      (node (ref "D5") (pin "3") (pinfunction "PF1-OSC_OUT_3") (pintype "passive"))
    )
    (net (code "77") (name "unconnected-(D7-SDO-Pad22)") (class "Default")
      (node (ref "D7") (pin "22") (pinfunction "SDO_22") (pintype "passive"))
    )
    (net (code "78") (name "unconnected-(D7-~{OUT0}-Pad5)") (class "Default")
      (node (ref "D7") (pin "5") (pinfunction "~{OUT0}_5") (pintype "passive"))
    )
    (net (code "79") (name "unconnected-(D7-~{OUT15}-Pad20)") (class "Default")
      (node (ref "D7") (pin "20") (pinfunction "~{OUT15}_20") (pintype "passive"))
    )
    (net (code "80") (name "unconnected-(X1-Pad2)") (class "Default")
      (node (ref "X1") (pin "2") (pinfunction "2_2") (pintype "passive"))
    )
    (net (code "81") (name "unconnected-(X1-Pad3)") (class "Default")
      (node (ref "X1") (pin "3") (pinfunction "3_3") (pintype "passive"))
    )
    (net (code "82") (name "unconnected-(X1-Pad4)") (class "Default")
      (node (ref "X1") (pin "4") (pinfunction "4_4") (pintype "passive"))
    )
  )
)
